# 1_MCU.net
KiCad netlist of a schematic drawn in Altium Designer
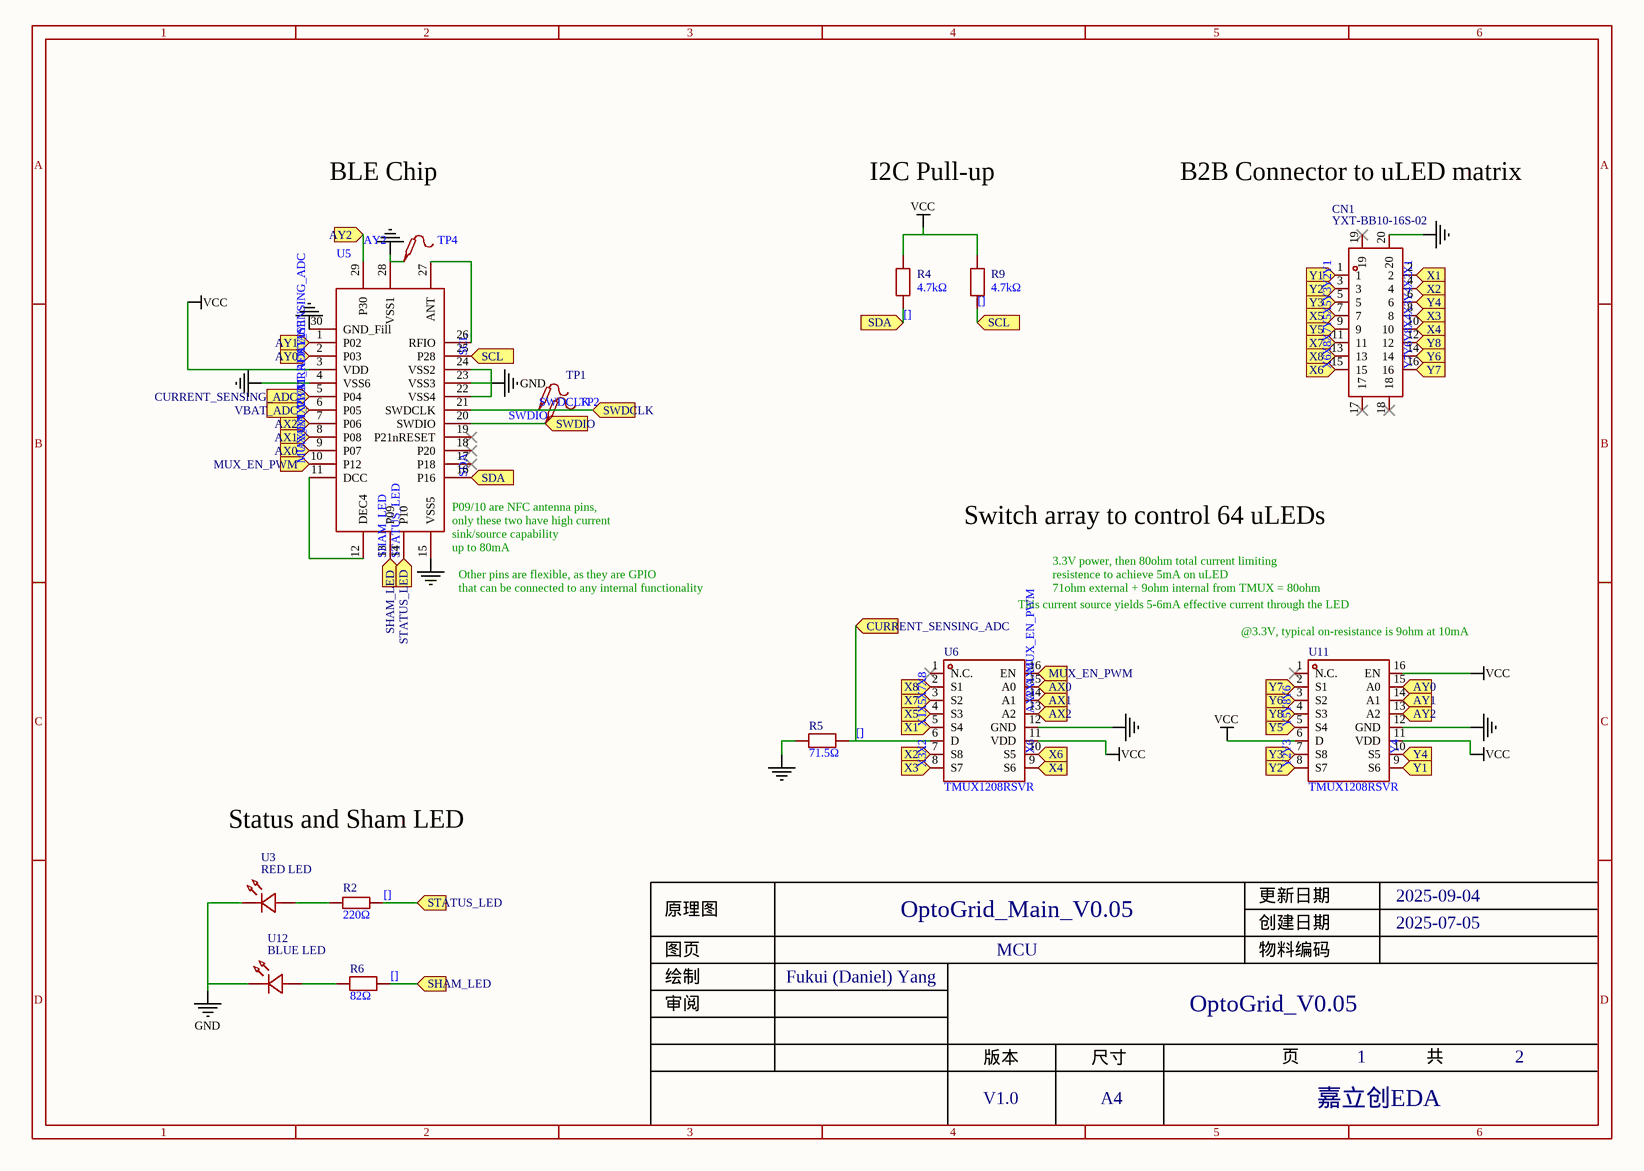
[diagram p0: 1_MCU.schdoc]

(export (version "E")
  (design (tool "Eeschema 10.0.6"))
  (components
    (comp (ref "CN1")
      (value "YXT-BB10-16S-02")
      (footprint "CONN-SMD_YXT-BB10-16S-02")
      (fields (field (name "MANUFACTURER") "YXT(益鑫通）"))
      (libsource (lib "altium-import") (part "root_0_YXT-BB10-16S-02_"))
    )
    (comp (ref "R2")
      (value "220Ω")
      (footprint "R0201")
      (fields
        (field (name "MANUFACTURER") "YAGEO(国巨)")
        (field (name "MANUFACTURER PART") "RC0201FR-07220RL")
        (field (name "TOLERANCE") "±1%")
      )
      (libsource (lib "altium-import") (part "root_0_RC0201FR-07220RL_"))
    )
    (comp (ref "R4")
      (value "4.7kΩ")
      (footprint "R0201")
      (fields
        (field (name "MANUFACTURER") "YAGEO(国巨)")
        (field (name "MANUFACTURER PART") "AF0201FR-074K7L")
        (field (name "TOLERANCE") "±1%")
      )
      (libsource (lib "altium-import") (part "root_1_AF0201FR-074K7L_"))
    )
    (comp (ref "R5")
      (value "71.5Ω")
      (footprint "R0201")
      (fields
        (field (name "MANUFACTURER") "UNI-ROYAL(厚声)")
        (field (name "MANUFACTURER PART") "0201WMF715JTEE")
        (field (name "TOLERANCE") "±1%")
      )
      (libsource (lib "altium-import") (part "root_0_0201WMF715JTEE_"))
    )
    (comp (ref "R6")
      (value "82Ω")
      (footprint "R0201")
      (fields
        (field (name "MANUFACTURER") "FH")
        (field (name "MANUFACTURER PART") "RC-01W82R0FT")
        (field (name "TOLERANCE") "±5%")
      )
      (libsource (lib "altium-import") (part "root_0_NQ01WMJ0820TEE_"))
    )
    (comp (ref "R9")
      (value "4.7kΩ")
      (footprint "R0201")
      (fields
        (field (name "MANUFACTURER") "YAGEO(国巨)")
        (field (name "MANUFACTURER PART") "AF0201FR-074K7L")
        (field (name "TOLERANCE") "±1%")
      )
      (libsource (lib "altium-import") (part "root_1_AF0201FR-074K7L_"))
    )
    (comp (ref "TP1")
      (value "~")
      (footprint "Test-Point-0.5mm")
      (libsource (lib "altium-import") (part "root_0_Test-Point_"))
    )
    (comp (ref "TP2")
      (value "~")
      (footprint "Test-Point-0.5mm")
      (libsource (lib "altium-import") (part "root_0_Test-Point_"))
    )
    (comp (ref "TP4")
      (value "~")
      (footprint "Test-Point-0.5mm")
      (libsource (lib "altium-import") (part "root_0_Test-Point_"))
    )
    (comp (ref "U3")
      (value "RED LED")
      (footprint "BLUE_LED_KINGBRIGHT_0201")
      (fields (field (name "MANUFACTURER") "Kingbright") (field (name "MANUFACTURER PART") "APG0603SURC-TT"))
      (libsource (lib "altium-import") (part "root_0_APG0603CGC-TT_"))
    )
    (comp (ref "U5")
      (value "~")
      (footprint "HY0020_footprint_NoFilling")
      (libsource (lib "altium-import") (part "root_0_HY0020_"))
    )
    (comp (ref "U6")
      (value "TMUX1208RSVR")
      (footprint "UTQFN-16_L2.6-W1.8-P0.40-BL")
      (fields (field (name "MANUFACTURER") "TI(德州仪器)"))
      (libsource (lib "altium-import") (part "root_0_TMUX1208RSVR_"))
    )
    (comp (ref "U11")
      (value "TMUX1208RSVR")
      (footprint "UTQFN-16_L2.6-W1.8-P0.40-BL")
      (fields (field (name "MANUFACTURER") "TI(德州仪器)"))
      (libsource (lib "altium-import") (part "root_0_TMUX1208RSVR_"))
    )
    (comp (ref "U12")
      (value "BLUE LED")
      (footprint "BLUE_LED_KINGBRIGHT_0201")
      (fields
        (field (name "MANUFACTURER") "Kingbright")
        (field (name "MANUFACTURER PART") "APG0603VBC-A1-5MAV")
      )
      (libsource (lib "altium-import") (part "root_0_APG0603CGC-TT_"))
    )
  )
  (nets
    (net (code "1") (name "/AX0") (class "Default")
      (node (ref "U5") (pin "9") (pinfunction "P07_9") (pintype "passive"))
      (node (ref "U6") (pin "15") (pinfunction "A0_15") (pintype "passive"))
    )
    (net (code "2") (name "/AX1") (class "Default")
      (node (ref "U5") (pin "8") (pinfunction "P08_8") (pintype "passive"))
      (node (ref "U6") (pin "14") (pinfunction "A1_14") (pintype "passive"))
    )
    (net (code "3") (name "/AX2") (class "Default")
      (node (ref "U5") (pin "7") (pinfunction "P06_7") (pintype "passive"))
      (node (ref "U6") (pin "13") (pinfunction "A2_13") (pintype "passive"))
    )
    (net (code "4") (name "/AY0") (class "Default")
      (node (ref "U11") (pin "15") (pinfunction "A0_15") (pintype "passive"))
      (node (ref "U5") (pin "2") (pinfunction "P03_2") (pintype "passive"))
    )
    (net (code "5") (name "/AY1") (class "Default")
      (node (ref "U11") (pin "14") (pinfunction "A1_14") (pintype "passive"))
      (node (ref "U5") (pin "1") (pinfunction "P02_1") (pintype "passive"))
    )
    (net (code "6") (name "/AY2") (class "Default")
      (node (ref "U11") (pin "13") (pinfunction "A2_13") (pintype "passive"))
      (node (ref "U5") (pin "29") (pinfunction "P30_29") (pintype "passive"))
    )
    (net (code "7") (name "/CURRENT_SENSING_ADC") (class "Default")
      (node (ref "R2") (pin "2") (pinfunction "2_2") (pintype "passive"))
      (node (ref "R4") (pin "1") (pinfunction "1_1") (pintype "passive"))
      (node (ref "R5") (pin "2") (pinfunction "2_2") (pintype "passive"))
      (node (ref "R6") (pin "2") (pinfunction "2_2") (pintype "passive"))
      (node (ref "R9") (pin "1") (pinfunction "1_1") (pintype "passive"))
      (node (ref "U5") (pin "13") (pinfunction "P09_13") (pintype "passive"))
      (node (ref "U5") (pin "14") (pinfunction "P10_14") (pintype "passive"))
      (node (ref "U5") (pin "16") (pinfunction "P16_16") (pintype "passive"))
      (node (ref "U5") (pin "25") (pinfunction "P28_25") (pintype "passive"))
      (node (ref "U5") (pin "5") (pinfunction "P04_5") (pintype "passive"))
      (node (ref "U6") (pin "6") (pinfunction "D_6") (pintype "passive"))
    )
    (net (code "8") (name "/MUX_EN_PWM") (class "Default")
      (node (ref "U5") (pin "10") (pinfunction "P12_10") (pintype "passive"))
      (node (ref "U6") (pin "16") (pinfunction "EN_16") (pintype "passive"))
    )
    (net (code "9") (name "/SWDCLK") (class "Default")
      (node (ref "TP1") (pin "1") (pinfunction "1_1") (pintype "passive"))
      (node (ref "U5") (pin "21") (pinfunction "SWDCLK_21") (pintype "passive"))
    )
    (net (code "10") (name "/SWDIO") (class "Default")
      (node (ref "TP2") (pin "1") (pinfunction "1_1") (pintype "passive"))
      (node (ref "U5") (pin "20") (pinfunction "SWDIO_20") (pintype "passive"))
    )
    (net (code "11") (name "/VBAT_ADC") (class "Default")
      (node (ref "U5") (pin "6") (pinfunction "P05_6") (pintype "passive"))
    )
    (net (code "12") (name "/X1") (class "Default")
      (node (ref "CN1") (pin "2") (pinfunction "2_2") (pintype "passive"))
      (node (ref "U6") (pin "5") (pinfunction "S4_5") (pintype "passive"))
    )
    (net (code "13") (name "/X2") (class "Default")
      (node (ref "CN1") (pin "4") (pinfunction "4_4") (pintype "passive"))
      (node (ref "U6") (pin "7") (pinfunction "S8_7") (pintype "passive"))
    )
    (net (code "14") (name "/X3") (class "Default")
      (node (ref "CN1") (pin "8") (pinfunction "8_8") (pintype "passive"))
      (node (ref "U6") (pin "8") (pinfunction "S7_8") (pintype "passive"))
    )
    (net (code "15") (name "/X4") (class "Default")
      (node (ref "CN1") (pin "10") (pinfunction "10_10") (pintype "passive"))
      (node (ref "U6") (pin "9") (pinfunction "S6_9") (pintype "passive"))
    )
    (net (code "16") (name "/X5") (class "Default")
      (node (ref "CN1") (pin "7") (pinfunction "7_7") (pintype "passive"))
      (node (ref "U6") (pin "4") (pinfunction "S3_4") (pintype "passive"))
    )
    (net (code "17") (name "/X6") (class "Default")
      (node (ref "CN1") (pin "15") (pinfunction "15_15") (pintype "passive"))
      (node (ref "U6") (pin "10") (pinfunction "S5_10") (pintype "passive"))
    )
    (net (code "18") (name "/X7") (class "Default")
      (node (ref "CN1") (pin "11") (pinfunction "11_11") (pintype "passive"))
      (node (ref "U6") (pin "3") (pinfunction "S2_3") (pintype "passive"))
    )
    (net (code "19") (name "/X8") (class "Default")
      (node (ref "CN1") (pin "13") (pinfunction "13_13") (pintype "passive"))
      (node (ref "U6") (pin "2") (pinfunction "S1_2") (pintype "passive"))
    )
    (net (code "20") (name "/Y1") (class "Default")
      (node (ref "CN1") (pin "1") (pinfunction "1_1") (pintype "passive"))
      (node (ref "U11") (pin "9") (pinfunction "S6_9") (pintype "passive"))
    )
    (net (code "21") (name "/Y2") (class "Default")
      (node (ref "CN1") (pin "3") (pinfunction "3_3") (pintype "passive"))
      (node (ref "U11") (pin "8") (pinfunction "S7_8") (pintype "passive"))
    )
    (net (code "22") (name "/Y3") (class "Default")
      (node (ref "CN1") (pin "5") (pinfunction "5_5") (pintype "passive"))
      (node (ref "U11") (pin "7") (pinfunction "S8_7") (pintype "passive"))
    )
    (net (code "23") (name "/Y4") (class "Default")
      (node (ref "CN1") (pin "6") (pinfunction "6_6") (pintype "passive"))
      (node (ref "U11") (pin "10") (pinfunction "S5_10") (pintype "passive"))
    )
    (net (code "24") (name "/Y5") (class "Default")
      (node (ref "CN1") (pin "9") (pinfunction "9_9") (pintype "passive"))
      (node (ref "U11") (pin "5") (pinfunction "S4_5") (pintype "passive"))
    )
    (net (code "25") (name "/Y6") (class "Default")
      (node (ref "CN1") (pin "14") (pinfunction "14_14") (pintype "passive"))
      (node (ref "U11") (pin "3") (pinfunction "S2_3") (pintype "passive"))
    )
    (net (code "26") (name "/Y7") (class "Default")
      (node (ref "CN1") (pin "16") (pinfunction "16_16") (pintype "passive"))
      (node (ref "U11") (pin "2") (pinfunction "S1_2") (pintype "passive"))
    )
    (net (code "27") (name "/Y8") (class "Default")
      (node (ref "CN1") (pin "12") (pinfunction "12_12") (pintype "passive"))
      (node (ref "U11") (pin "4") (pinfunction "S3_4") (pintype "passive"))
    )
    (net (code "28") (name "GND") (class "Default")
      (node (ref "CN1") (pin "20") (pinfunction "20_20") (pintype "passive"))
      (node (ref "R5") (pin "1") (pinfunction "1_1") (pintype "passive"))
      (node (ref "TP4") (pin "1") (pinfunction "1_1") (pintype "passive"))
      (node (ref "U11") (pin "12") (pinfunction "GND_12") (pintype "passive"))
      (node (ref "U12") (pin "1") (pinfunction "K_1") (pintype "passive"))
      (node (ref "U3") (pin "1") (pinfunction "K_1") (pintype "passive"))
      (node (ref "U5") (pin "15") (pinfunction "VSS5_15") (pintype "passive"))
      (node (ref "U5") (pin "22") (pinfunction "VSS4_22") (pintype "passive"))
      (node (ref "U5") (pin "23") (pinfunction "VSS3_23") (pintype "passive"))
      (node (ref "U5") (pin "24") (pinfunction "VSS2_24") (pintype "passive"))
      (node (ref "U5") (pin "28") (pinfunction "VSS1_28") (pintype "passive"))
      (node (ref "U5") (pin "30") (pinfunction "GND_Fill_30") (pintype "passive"))
      (node (ref "U5") (pin "4") (pinfunction "VSS6_4") (pintype "passive"))
      (node (ref "U6") (pin "12") (pinfunction "GND_12") (pintype "passive"))
    )
    (net (code "29") (name "Net-(U3-A)") (class "Default")
      (node (ref "R2") (pin "1") (pinfunction "1_1") (pintype "passive"))
      (node (ref "U3") (pin "2") (pinfunction "A_2") (pintype "passive"))
    )
    (net (code "30") (name "Net-(U5-ANT)") (class "Default")
      (node (ref "U5") (pin "26") (pinfunction "RFIO_26") (pintype "passive"))
      (node (ref "U5") (pin "27") (pinfunction "ANT_27") (pintype "passive"))
    )
    (net (code "31") (name "Net-(U5-DCC)") (class "Default")
      (node (ref "U5") (pin "11") (pinfunction "DCC_11") (pintype "passive"))
      (node (ref "U5") (pin "12") (pinfunction "DEC4_12") (pintype "passive"))
    )
    (net (code "32") (name "Net-(U12-A)") (class "Default")
      (node (ref "R6") (pin "1") (pinfunction "1_1") (pintype "passive"))
      (node (ref "U12") (pin "2") (pinfunction "A_2") (pintype "passive"))
    )
    (net (code "33") (name "VCC") (class "Default")
      (node (ref "R4") (pin "2") (pinfunction "2_2") (pintype "passive"))
      (node (ref "R9") (pin "2") (pinfunction "2_2") (pintype "passive"))
      (node (ref "U11") (pin "11") (pinfunction "VDD_11") (pintype "passive"))
      (node (ref "U11") (pin "16") (pinfunction "EN_16") (pintype "passive"))
      (node (ref "U11") (pin "6") (pinfunction "D_6") (pintype "passive"))
      (node (ref "U5") (pin "3") (pinfunction "VDD_3") (pintype "passive"))
      (node (ref "U6") (pin "11") (pinfunction "VDD_11") (pintype "passive"))
    )
    (net (code "34") (name "unconnected-(CN1-Pad17)") (class "Default")
      (node (ref "CN1") (pin "17") (pinfunction "17_17") (pintype "passive+no_connect"))
    )
    (net (code "35") (name "unconnected-(CN1-Pad18)") (class "Default")
      (node (ref "CN1") (pin "18") (pinfunction "18_18") (pintype "passive+no_connect"))
    )
    (net (code "36") (name "unconnected-(CN1-Pad19)") (class "Default")
      (node (ref "CN1") (pin "19") (pinfunction "19_19") (pintype "passive+no_connect"))
    )
    (net (code "37") (name "unconnected-(U5-P18-Pad17)") (class "Default")
      (node (ref "U5") (pin "17") (pinfunction "P18_17") (pintype "passive+no_connect"))
    )
    (net (code "38") (name "unconnected-(U5-P20-Pad18)") (class "Default")
      (node (ref "U5") (pin "18") (pinfunction "P20_18") (pintype "passive+no_connect"))
    )
    (net (code "39") (name "unconnected-(U5-P21nRESET-Pad19)") (class "Default")
      (node (ref "U5") (pin "19") (pinfunction "P21nRESET_19") (pintype "passive+no_connect"))
    )
    (net (code "40") (name "unconnected-(U6-N.C.-Pad1)") (class "Default")
      (node (ref "U6") (pin "1") (pinfunction "N.C._1") (pintype "passive+no_connect"))
    )
    (net (code "41") (name "unconnected-(U11-N.C.-Pad1)") (class "Default")
      (node (ref "U11") (pin "1") (pinfunction "N.C._1") (pintype "passive+no_connect"))
    )
  )
)
